# ant_amplifier.net
KiCad netlist of a schematic drawn in Altium Designer
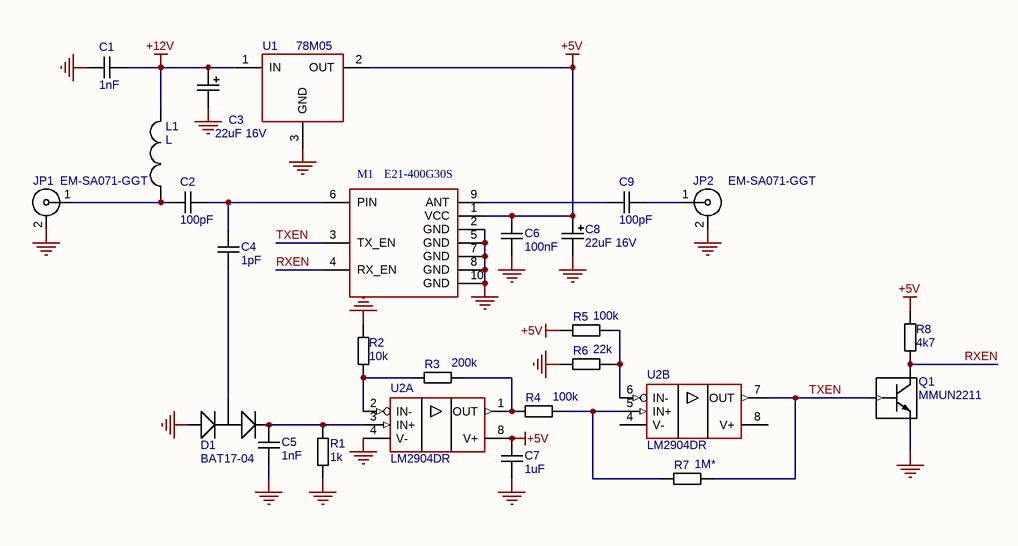
[diagram p0: ant_amplifier.SchDoc]

(export (version "E")
  (design (tool "Eeschema 10.0.6"))
  (components
    (comp (ref "C1")
      (value "1nF")
      (footprint "C-0603")
      (fields (field (name "VOLTAGE") "50V"))
      (libsource (lib "Passive") (part "CAPN"))
    )
    (comp (ref "C2")
      (value "100pF")
      (footprint "C-0603")
      (fields (field (name "VOLTAGE") "50V"))
      (libsource (lib "Passive") (part "CAPN"))
    )
    (comp (ref "C3")
      (value "22uF 16V")
      (footprint "C_TANTAL_B")
      (fields (field (name "VOLTAGE") "16V"))
      (libsource (lib "Passive") (part "CAPP"))
    )
    (comp (ref "C4")
      (value "1pF")
      (footprint "C-0603")
      (fields (field (name "VOLTAGE") "50V"))
      (libsource (lib "Passive") (part "CAPN"))
    )
    (comp (ref "C5")
      (value "1nF")
      (footprint "C-0603")
      (fields (field (name "VOLTAGE") "50V"))
      (libsource (lib "Passive") (part "CAPN"))
    )
    (comp (ref "C6")
      (value "100nF")
      (footprint "C-0603")
      (fields (field (name "VOLTAGE") "50V"))
      (libsource (lib "Passive") (part "CAPN"))
    )
    (comp (ref "C7")
      (value "1uF")
      (footprint "C-0603")
      (fields (field (name "VOLTAGE") "50V"))
      (libsource (lib "Passive") (part "CAPN"))
    )
    (comp (ref "C8")
      (value "22uF 16V")
      (footprint "C_TANTAL_B")
      (fields (field (name "VOLTAGE") "16V"))
      (libsource (lib "Passive") (part "CAPP"))
    )
    (comp (ref "C9")
      (value "100pF")
      (footprint "C-0603")
      (fields (field (name "VOLTAGE") "50V"))
      (libsource (lib "Passive") (part "CAPN"))
    )
    (comp (ref "D1") (value "BAT17-04") (footprint "SOT-23") (libsource (lib "Diodes") (part "BAT17-04")))
    (comp (ref "JP1")
      (value "EM-SA071-GGT")
      (footprint "SMA_F_EDGE")
      (description "SMA Female R/A PCB Mount")
      (libsource (lib "Connectors") (part "SMA"))
    )
    (comp (ref "JP2")
      (value "EM-SA071-GGT")
      (footprint "SMA_F_EDGE")
      (description "SMA Female R/A PCB Mount")
      (libsource (lib "Connectors") (part "SMA"))
    )
    (comp (ref "L1") (value "L") (footprint "L-1210") (libsource (lib "Passive") (part "L")))
    (comp (ref "M1") (value "E21-400G30S") (footprint "E21") (libsource (lib "RFmodules") (part "E21")))
    (comp (ref "Q1")
      (value "MMUN2211")
      (footprint "SOT-23")
      (libsource (lib "Transistors") (part "MMUN2211"))
    )
    (comp (ref "R1") (value "1k") (footprint "R-0603") (libsource (lib "") (part "RES_1")))
    (comp (ref "R2") (value "10k") (footprint "R-0603") (libsource (lib "") (part "RES_1")))
    (comp (ref "R3") (value "200k") (footprint "R-0603") (libsource (lib "") (part "RES_2")))
    (comp (ref "R4") (value "100k") (footprint "R-0603") (libsource (lib "") (part "RES_2")))
    (comp (ref "R5") (value "100k") (footprint "R-0603") (libsource (lib "Passive") (part "RES")))
    (comp (ref "R6") (value "22k") (footprint "R-0603") (libsource (lib "Passive") (part "RES")))
    (comp (ref "R7") (value "1M*") (footprint "R-0603") (libsource (lib "Passive") (part "RES")))
    (comp (ref "R8") (value "4k7") (footprint "R-0603") (libsource (lib "") (part "RES_1")))
    (comp (ref "U1") (value "78M05") (footprint "DPAK3") (libsource (lib "ICs") (part "78M08")))
    (comp (ref "U2")
      (value "LM2904DR")
      (footprint "SO-8")
      (description "Dual Operational Amplifiers, SOIC-8")
      (libsource (lib "ICs") (part "LM2904"))
    )
  )
  (nets
    (net (code "1") (name "+5V") (class "Default")
      (node (ref "C6") (pin "1") (pinfunction "1_1") (pintype "passive"))
      (node (ref "C7") (pin "1") (pinfunction "1_1") (pintype "passive"))
      (node (ref "C8") (pin "2") (pinfunction "2_2") (pintype "passive"))
      (node (ref "M1") (pin "1") (pinfunction "VCC_1") (pintype "passive"))
      (node (ref "R5") (pin "1") (pinfunction "1_1") (pintype "passive"))
      (node (ref "R8") (pin "2") (pinfunction "2_2") (pintype "passive"))
      (node (ref "U1") (pin "2") (pinfunction "OUT_2") (pintype "passive"))
      (node (ref "U2") (pin "8") (pinfunction "V+_8") (pintype "power_in"))
    )
    (net (code "2") (name "+12V") (class "Default")
      (node (ref "C1") (pin "2") (pinfunction "2_2") (pintype "passive"))
      (node (ref "C3") (pin "2") (pinfunction "2_2") (pintype "passive"))
      (node (ref "L1") (pin "2") (pinfunction "2_2") (pintype "passive"))
      (node (ref "U1") (pin "1") (pinfunction "IN_1") (pintype "passive"))
    )
    (net (code "3") (name "/RXEN") (class "Default")
      (node (ref "M1") (pin "4") (pinfunction "RX_EN_4") (pintype "passive"))
      (node (ref "Q1") (pin "3") (pinfunction "COLLECTOR_3") (pintype "passive"))
      (node (ref "R8") (pin "1") (pinfunction "1_1") (pintype "passive"))
    )
    (net (code "4") (name "/TXEN") (class "Default")
      (node (ref "M1") (pin "3") (pinfunction "TX_EN_3") (pintype "passive"))
      (node (ref "Q1") (pin "1") (pinfunction "BASE_1") (pintype "input"))
      (node (ref "R7") (pin "2") (pinfunction "2_2") (pintype "passive"))
      (node (ref "U2") (pin "7") (pinfunction "OUT_7") (pintype "output"))
    )
    (net (code "5") (name "GND") (class "Default")
      (node (ref "C1") (pin "1") (pinfunction "1_1") (pintype "passive"))
      (node (ref "C3") (pin "1") (pinfunction "1_1") (pintype "passive"))
      (node (ref "C5") (pin "2") (pinfunction "2_2") (pintype "passive"))
      (node (ref "C6") (pin "2") (pinfunction "2_2") (pintype "passive"))
      (node (ref "C7") (pin "2") (pinfunction "2_2") (pintype "passive"))
      (node (ref "C8") (pin "1") (pinfunction "1_1") (pintype "passive"))
      (node (ref "D1") (pin "1") (pinfunction "1_1") (pintype "passive"))
      (node (ref "JP1") (pin "2") (pinfunction "2_2") (pintype "passive"))
      (node (ref "JP2") (pin "2") (pinfunction "2_2") (pintype "passive"))
      (node (ref "M1") (pin "10") (pinfunction "GND_10") (pintype "passive"))
      (node (ref "M1") (pin "2") (pinfunction "GND_2") (pintype "passive"))
      (node (ref "M1") (pin "5") (pinfunction "GND_5") (pintype "passive"))
      (node (ref "M1") (pin "7") (pinfunction "GND_7") (pintype "passive"))
      (node (ref "M1") (pin "8") (pinfunction "GND_8") (pintype "passive"))
      (node (ref "Q1") (pin "2") (pinfunction "EMITTER_2") (pintype "passive"))
      (node (ref "R1") (pin "1") (pinfunction "1_1") (pintype "passive"))
      (node (ref "R2") (pin "2") (pinfunction "2_2") (pintype "passive"))
      (node (ref "R6") (pin "1") (pinfunction "1_1") (pintype "passive"))
      (node (ref "U1") (pin "3") (pinfunction "GND_3") (pintype "passive"))
      (node (ref "U2") (pin "4") (pinfunction "V-_4") (pintype "power_in"))
    )
    (net (code "6") (name "Net-(C2-Pad1)") (class "Default")
      (node (ref "C2") (pin "1") (pinfunction "1_1") (pintype "passive"))
      (node (ref "JP1") (pin "1") (pinfunction "1_1") (pintype "passive"))
      (node (ref "L1") (pin "1") (pinfunction "1_1") (pintype "passive"))
    )
    (net (code "7") (name "Net-(C4-Pad2)") (class "Default")
      (node (ref "C4") (pin "2") (pinfunction "2_2") (pintype "passive"))
      (node (ref "D1") (pin "3") (pinfunction "3_3") (pintype "passive"))
    )
    (net (code "8") (name "Net-(C9-Pad2)") (class "Default")
      (node (ref "C9") (pin "2") (pinfunction "2_2") (pintype "passive"))
      (node (ref "JP2") (pin "1") (pinfunction "1_1") (pintype "passive"))
    )
    (net (code "9") (name "Net-(M1-ANT)") (class "Default")
      (node (ref "C9") (pin "1") (pinfunction "1_1") (pintype "passive"))
      (node (ref "M1") (pin "9") (pinfunction "ANT_9") (pintype "passive"))
    )
    (net (code "10") (name "Net-(M1-PIN)") (class "Default")
      (node (ref "C2") (pin "2") (pinfunction "2_2") (pintype "passive"))
      (node (ref "C4") (pin "1") (pinfunction "1_1") (pintype "passive"))
      (node (ref "M1") (pin "6") (pinfunction "PIN_6") (pintype "passive"))
    )
    (net (code "11") (name "Net-(U2A-IN+)") (class "Default")
      (node (ref "C5") (pin "1") (pinfunction "1_1") (pintype "passive"))
      (node (ref "D1") (pin "2") (pinfunction "3_2") (pintype "passive"))
      (node (ref "R1") (pin "2") (pinfunction "2_2") (pintype "passive"))
      (node (ref "U2") (pin "3") (pinfunction "IN+_3") (pintype "input"))
    )
    (net (code "12") (name "Net-(U2A-IN-)") (class "Default")
      (node (ref "R2") (pin "1") (pinfunction "1_1") (pintype "passive"))
      (node (ref "R3") (pin "2") (pinfunction "2_2") (pintype "passive"))
      (node (ref "U2") (pin "2") (pinfunction "IN-_2") (pintype "input"))
    )
    (net (code "13") (name "Net-(U2A-OUT)") (class "Default")
      (node (ref "R3") (pin "1") (pinfunction "1_1") (pintype "passive"))
      (node (ref "R4") (pin "2") (pinfunction "2_2") (pintype "passive"))
      (node (ref "U2") (pin "1") (pinfunction "OUT_1") (pintype "output"))
    )
    (net (code "14") (name "Net-(U2B-IN+)") (class "Default")
      (node (ref "R4") (pin "1") (pinfunction "1_1") (pintype "passive"))
      (node (ref "R7") (pin "1") (pinfunction "1_1") (pintype "passive"))
      (node (ref "U2") (pin "5") (pinfunction "IN+_5") (pintype "input"))
    )
    (net (code "15") (name "Net-(U2B-IN-)") (class "Default")
      (node (ref "R5") (pin "2") (pinfunction "2_2") (pintype "passive"))
      (node (ref "R6") (pin "2") (pinfunction "2_2") (pintype "passive"))
      (node (ref "U2") (pin "6") (pinfunction "IN-_6") (pintype "input"))
    )
    (net (code "16") (name "unconnected-(U2B-V+-Pad8)") (class "Default")
      (node (ref "U2") (pin "8") (pinfunction "V+_8") (pintype "power_in"))
    )
    (net (code "17") (name "unconnected-(U2B-V--Pad4)") (class "Default")
      (node (ref "U2") (pin "4") (pinfunction "V-_4") (pintype "power_in"))
    )
  )
)
